# laminator.net
KiCad netlist of a schematic drawn in EAGLE
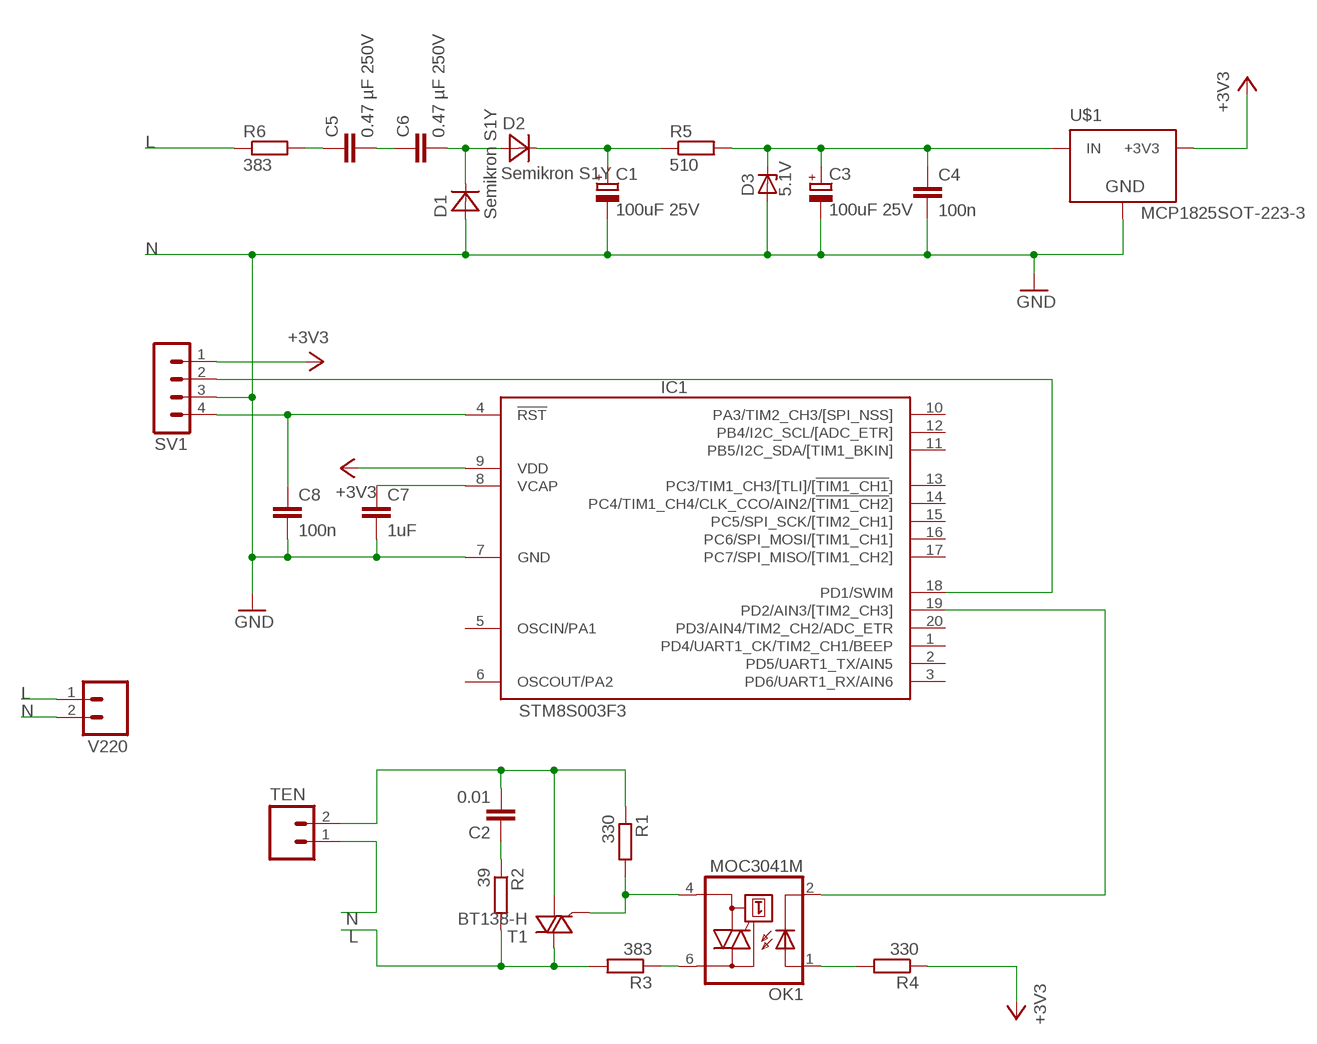
[diagram p0: schematic, sheet 1]

(export (version "E")
  (design (tool "Eeschema 10.0.6"))
  (components
    (comp (ref "C1")
      (value "100uF 25V")
      (footprint "eagle-import:E2,5-6")
      (libsource (lib "eagle-import") (part "CPOL-EUE2.5-6"))
    )
    (comp (ref "C2")
      (value "0.01")
      (footprint "eagle-import:C050-025X075")
      (libsource (lib "eagle-import") (part "C-EU050-025X075"))
    )
    (comp (ref "C3")
      (value "100uF 25V")
      (footprint "eagle-import:E2,5-6")
      (libsource (lib "eagle-import") (part "CPOL-EUE2.5-6"))
    )
    (comp (ref "C4")
      (value "100n")
      (footprint "eagle-import:C0805")
      (libsource (lib "eagle-import") (part "C-EUC0805"))
    )
    (comp (ref "C5")
      (value "0.47 µF 250V")
      (footprint "eagle-import:C150-072X183")
      (libsource (lib "eagle-import") (part "C-EU150-072X183"))
    )
    (comp (ref "C6")
      (value "0.47 µF 250V")
      (footprint "eagle-import:C150-072X183")
      (libsource (lib "eagle-import") (part "C-EU150-072X183"))
    )
    (comp (ref "C7")
      (value "1uF")
      (footprint "eagle-import:C0805")
      (libsource (lib "eagle-import") (part "C-EUC0805"))
    )
    (comp (ref "C8")
      (value "100n")
      (footprint "eagle-import:C0805")
      (libsource (lib "eagle-import") (part "C-EUC0805"))
    )
    (comp (ref "D1")
      (value "Semikron S1Y")
      (footprint "eagle-import:SMA")
      (libsource (lib "eagle-import") (part "MBRA340T3"))
    )
    (comp (ref "D2")
      (value "Semikron S1Y")
      (footprint "eagle-import:SMA")
      (libsource (lib "eagle-import") (part "MBRA340T3"))
    )
    (comp (ref "D3")
      (value "5.1V")
      (footprint "eagle-import:SMB")
      (libsource (lib "eagle-import") (part "ZENER-DIODESMB"))
    )
    (comp (ref "IC1")
      (value "STM8S003F3")
      (footprint "eagle-import:TSSOP20")
      (libsource (lib "eagle-import") (part "STM8S003F3"))
    )
    (comp (ref "OK1")
      (value "MOC3041M")
      (footprint "eagle-import:DIL06")
      (fields (field (name "MF") "FAIRCHILD SEMICONDUCTOR"))
      (libsource (lib "eagle-import") (part "MOC3041M"))
    )
    (comp (ref "R1")
      (value "330")
      (footprint "eagle-import:0207_7")
      (libsource (lib "eagle-import") (part "R-EU_0207/7"))
    )
    (comp (ref "R2")
      (value "39")
      (footprint "eagle-import:0207_7")
      (libsource (lib "eagle-import") (part "R-EU_0207/7"))
    )
    (comp (ref "R3")
      (value "383")
      (footprint "eagle-import:0207_7")
      (libsource (lib "eagle-import") (part "R-EU_0207/7"))
    )
    (comp (ref "R4")
      (value "330")
      (footprint "eagle-import:R1206")
      (libsource (lib "eagle-import") (part "R-EU_R1206"))
    )
    (comp (ref "R5")
      (value "510")
      (footprint "eagle-import:R0805")
      (libsource (lib "eagle-import") (part "R-EU_R0805"))
    )
    (comp (ref "R6")
      (value "383")
      (footprint "eagle-import:0207_7")
      (libsource (lib "eagle-import") (part "R-EU_0207/7"))
    )
    (comp (ref "SV1")
      (value "MA04-1")
      (footprint "eagle-import:MA04-1")
      (libsource (lib "eagle-import") (part "MA04-1"))
    )
    (comp (ref "T1")
      (value "BT138-H")
      (footprint "eagle-import:TO220BH")
      (libsource (lib "eagle-import") (part "BT138-H"))
    )
    (comp (ref "TEN")
      (value "M02")
      (footprint "eagle-import:02P")
      (libsource (lib "eagle-import") (part "M02"))
    )
    (comp (ref "U$1")
      (value "MCP1825SOT-223-3")
      (footprint "eagle-import:SOT-223")
      (libsource (lib "eagle-import") (part "MCP1825SOT-223-3"))
    )
    (comp (ref "V220")
      (value "M02")
      (footprint "eagle-import:02P")
      (libsource (lib "eagle-import") (part "M02"))
    )
  )
  (nets
    (net (code "1") (name "+3V3") (class "Default")
      (node (ref "IC1") (pin "9") (pinfunction "VDD_9") (pintype "power_in"))
      (node (ref "R4") (pin "1") (pinfunction "1_1") (pintype "passive"))
      (node (ref "SV1") (pin "1") (pinfunction "1_1") (pintype "passive"))
      (node (ref "U$1") (pin "3") (pinfunction "+3V3_3") (pintype "power_in"))
    )
    (net (code "2") (name "/L") (class "Default")
      (node (ref "R2") (pin "2") (pinfunction "2_2") (pintype "passive"))
      (node (ref "R3") (pin "2") (pinfunction "2_2") (pintype "passive"))
      (node (ref "R6") (pin "1") (pinfunction "1_1") (pintype "passive"))
      (node (ref "T1") (pin "T2") (pinfunction "A2_T2") (pintype "passive"))
      (node (ref "V220") (pin "1") (pinfunction "1_1") (pintype "passive"))
    )
    (net (code "3") (name "GND") (class "Default")
      (node (ref "C1") (pin "-") (pinfunction "-_-") (pintype "passive"))
      (node (ref "C3") (pin "-") (pinfunction "-_-") (pintype "passive"))
      (node (ref "C4") (pin "2") (pinfunction "2_2") (pintype "passive"))
      (node (ref "C7") (pin "2") (pinfunction "2_2") (pintype "passive"))
      (node (ref "C8") (pin "2") (pinfunction "2_2") (pintype "passive"))
      (node (ref "D1") (pin "A") (pinfunction "A_A") (pintype "passive"))
      (node (ref "D3") (pin "A") (pinfunction "A_A") (pintype "passive"))
      (node (ref "IC1") (pin "7") (pinfunction "GND_7") (pintype "power_in"))
      (node (ref "SV1") (pin "3") (pinfunction "3_3") (pintype "passive"))
      (node (ref "TEN") (pin "1") (pinfunction "1_1") (pintype "passive"))
      (node (ref "U$1") (pin "2") (pinfunction "GND_2") (pintype "power_in"))
      (node (ref "V220") (pin "2") (pinfunction "2_2") (pintype "passive"))
    )
    (net (code "4") (name "Net-(C1-Pad+)") (class "Default")
      (node (ref "C1") (pin "+") (pinfunction "+_+") (pintype "passive"))
      (node (ref "D2") (pin "C") (pinfunction "C_C") (pintype "passive"))
      (node (ref "R5") (pin "1") (pinfunction "1_1") (pintype "passive"))
    )
    (net (code "5") (name "Net-(C2-Pad1)") (class "Default")
      (node (ref "C2") (pin "1") (pinfunction "1_1") (pintype "passive"))
      (node (ref "R2") (pin "1") (pinfunction "1_1") (pintype "passive"))
    )
    (net (code "6") (name "Net-(C5-Pad1)") (class "Default")
      (node (ref "C5") (pin "1") (pinfunction "1_1") (pintype "passive"))
      (node (ref "R6") (pin "2") (pinfunction "2_2") (pintype "passive"))
    )
    (net (code "7") (name "Net-(C5-Pad2)") (class "Default")
      (node (ref "C5") (pin "2") (pinfunction "2_2") (pintype "passive"))
      (node (ref "C6") (pin "1") (pinfunction "1_1") (pintype "passive"))
    )
    (net (code "8") (name "Net-(C6-Pad2)") (class "Default")
      (node (ref "C6") (pin "2") (pinfunction "2_2") (pintype "passive"))
      (node (ref "D1") (pin "C") (pinfunction "C_C") (pintype "passive"))
      (node (ref "D2") (pin "A") (pinfunction "A_A") (pintype "passive"))
    )
    (net (code "9") (name "Net-(IC1-PD1{slash}SWIM)") (class "Default")
      (node (ref "IC1") (pin "18") (pinfunction "PD1/SWIM_18") (pintype "bidirectional"))
      (node (ref "SV1") (pin "2") (pinfunction "2_2") (pintype "passive"))
    )
    (net (code "10") (name "Net-(IC1-PD2{slash}AIN3{slash}[TIM2_CH3])") (class "Default")
      (node (ref "IC1") (pin "19") (pinfunction "PD2/AIN3/[TIM2_CH3]_19") (pintype "bidirectional"))
      (node (ref "OK1") (pin "2") (pinfunction "C_2") (pintype "passive"))
    )
    (net (code "11") (name "Net-(IC1-VCAP)") (class "Default")
      (node (ref "C7") (pin "1") (pinfunction "1_1") (pintype "passive"))
      (node (ref "IC1") (pin "8") (pinfunction "VCAP_8") (pintype "power_in"))
    )
    (net (code "12") (name "Net-(IC1-~{RST})") (class "Default")
      (node (ref "C8") (pin "1") (pinfunction "1_1") (pintype "passive"))
      (node (ref "IC1") (pin "4") (pinfunction "~{RST}_4") (pintype "input"))
      (node (ref "SV1") (pin "4") (pinfunction "4_4") (pintype "passive"))
    )
    (net (code "13") (name "Net-(OK1-A)") (class "Default")
      (node (ref "OK1") (pin "1") (pinfunction "A_1") (pintype "passive"))
      (node (ref "R4") (pin "2") (pinfunction "2_2") (pintype "passive"))
    )
    (net (code "14") (name "Net-(OK1-A1)") (class "Default")
      (node (ref "OK1") (pin "4") (pinfunction "A1_4") (pintype "passive"))
      (node (ref "R1") (pin "2") (pinfunction "2_2") (pintype "passive"))
      (node (ref "T1") (pin "G") (pinfunction "G_G") (pintype "passive"))
    )
    (net (code "15") (name "Net-(OK1-A2)") (class "Default")
      (node (ref "OK1") (pin "6") (pinfunction "A2_6") (pintype "passive"))
      (node (ref "R3") (pin "1") (pinfunction "1_1") (pintype "passive"))
    )
    (net (code "16") (name "Net-(T1-A1)") (class "Default")
      (node (ref "C2") (pin "2") (pinfunction "2_2") (pintype "passive"))
      (node (ref "R1") (pin "1") (pinfunction "1_1") (pintype "passive"))
      (node (ref "T1") (pin "T1") (pinfunction "A1_T1") (pintype "passive"))
      (node (ref "TEN") (pin "2") (pinfunction "2_2") (pintype "passive"))
    )
    (net (code "17") (name "Net-(U$1-IN)") (class "Default")
      (node (ref "C3") (pin "+") (pinfunction "+_+") (pintype "passive"))
      (node (ref "C4") (pin "1") (pinfunction "1_1") (pintype "passive"))
      (node (ref "D3") (pin "C") (pinfunction "C_C") (pintype "passive"))
      (node (ref "R5") (pin "2") (pinfunction "2_2") (pintype "passive"))
      (node (ref "U$1") (pin "1") (pinfunction "IN_1") (pintype "power_in"))
    )
    (net (code "18") (name "unconnected-(IC1-OSCIN{slash}PA1-Pad5)") (class "Default")
      (node (ref "IC1") (pin "5") (pinfunction "OSCIN/PA1_5") (pintype "bidirectional"))
    )
    (net (code "19") (name "unconnected-(IC1-OSCOUT{slash}PA2-Pad6)") (class "Default")
      (node (ref "IC1") (pin "6") (pinfunction "OSCOUT/PA2_6") (pintype "bidirectional"))
    )
    (net (code "20") (name "unconnected-(IC1-PA3{slash}TIM2_CH3{slash}[SPI_NSS]-Pad10)") (class "Default")
      (node (ref "IC1") (pin "10") (pinfunction "PA3/TIM2_CH3/[SPI_NSS]_10") (pintype "bidirectional"))
    )
    (net (code "21") (name "unconnected-(IC1-PB4{slash}I2C_SCL{slash}[ADC_ETR]-Pad12)") (class "Default")
      (node (ref "IC1") (pin "12") (pinfunction "PB4/I2C_SCL/[ADC_ETR]_12") (pintype "bidirectional"))
    )
    (net (code "22") (name "unconnected-(IC1-PB5{slash}I2C_SDA{slash}[TIM1_BKIN]-Pad11)") (class "Default")
      (node (ref "IC1") (pin "11") (pinfunction "PB5/I2C_SDA/[TIM1_BKIN]_11") (pintype "bidirectional"))
    )
    (net (code "23") (name "unconnected-(IC1-PC3{slash}TIM1_CH3{slash}[TLI]{slash}[~{TIM1_CH1}]-Pad13)") (class "Default")
      (node (ref "IC1") (pin "13") (pinfunction "PC3/TIM1_CH3/[TLI]/[~{TIM1_CH1}]_13") (pintype "bidirectional"))
    )
    (net (code "24") (name "unconnected-(IC1-PC4{slash}TIM1_CH4{slash}CLK_CCO{slash}AIN2{slash}[~{TIM1_CH2}]-Pad14)") (class "Default")
      (node (ref "IC1") (pin "14") (pinfunction "PC4/TIM1_CH4/CLK_CCO/AIN2/[~{TIM1_CH2}]_14") (pintype "bidirectional"))
    )
    (net (code "25") (name "unconnected-(IC1-PC5{slash}SPI_SCK{slash}[TIM2_CH1]-Pad15)") (class "Default")
      (node (ref "IC1") (pin "15") (pinfunction "PC5/SPI_SCK/[TIM2_CH1]_15") (pintype "bidirectional"))
    )
    (net (code "26") (name "unconnected-(IC1-PC6{slash}SPI_MOSI{slash}[TIM1_CH1]-Pad16)") (class "Default")
      (node (ref "IC1") (pin "16") (pinfunction "PC6/SPI_MOSI/[TIM1_CH1]_16") (pintype "bidirectional"))
    )
    (net (code "27") (name "unconnected-(IC1-PC7{slash}SPI_MISO{slash}[TIM1_CH2]-Pad17)") (class "Default")
      (node (ref "IC1") (pin "17") (pinfunction "PC7/SPI_MISO/[TIM1_CH2]_17") (pintype "bidirectional"))
    )
    (net (code "28") (name "unconnected-(IC1-PD3{slash}AIN4{slash}TIM2_CH2{slash}ADC_ETR-Pad20)") (class "Default")
      (node (ref "IC1") (pin "20") (pinfunction "PD3/AIN4/TIM2_CH2/ADC_ETR_20") (pintype "bidirectional"))
    )
    (net (code "29") (name "unconnected-(IC1-PD4{slash}UART1_CK{slash}TIM2_CH1{slash}BEEP-Pad1)") (class "Default")
      (node (ref "IC1") (pin "1") (pinfunction "PD4/UART1_CK/TIM2_CH1/BEEP_1") (pintype "bidirectional"))
    )
    (net (code "30") (name "unconnected-(IC1-PD5{slash}UART1_TX{slash}AIN5-Pad2)") (class "Default")
      (node (ref "IC1") (pin "2") (pinfunction "PD5/UART1_TX/AIN5_2") (pintype "bidirectional"))
    )
    (net (code "31") (name "unconnected-(IC1-PD6{slash}UART1_RX{slash}AIN6-Pad3)") (class "Default")
      (node (ref "IC1") (pin "3") (pinfunction "PD6/UART1_RX/AIN6_3") (pintype "bidirectional"))
    )
  )
)
